# rotary-encoder-breakout-mk-2_0.net
KiCad netlist of a schematic drawn in EAGLE
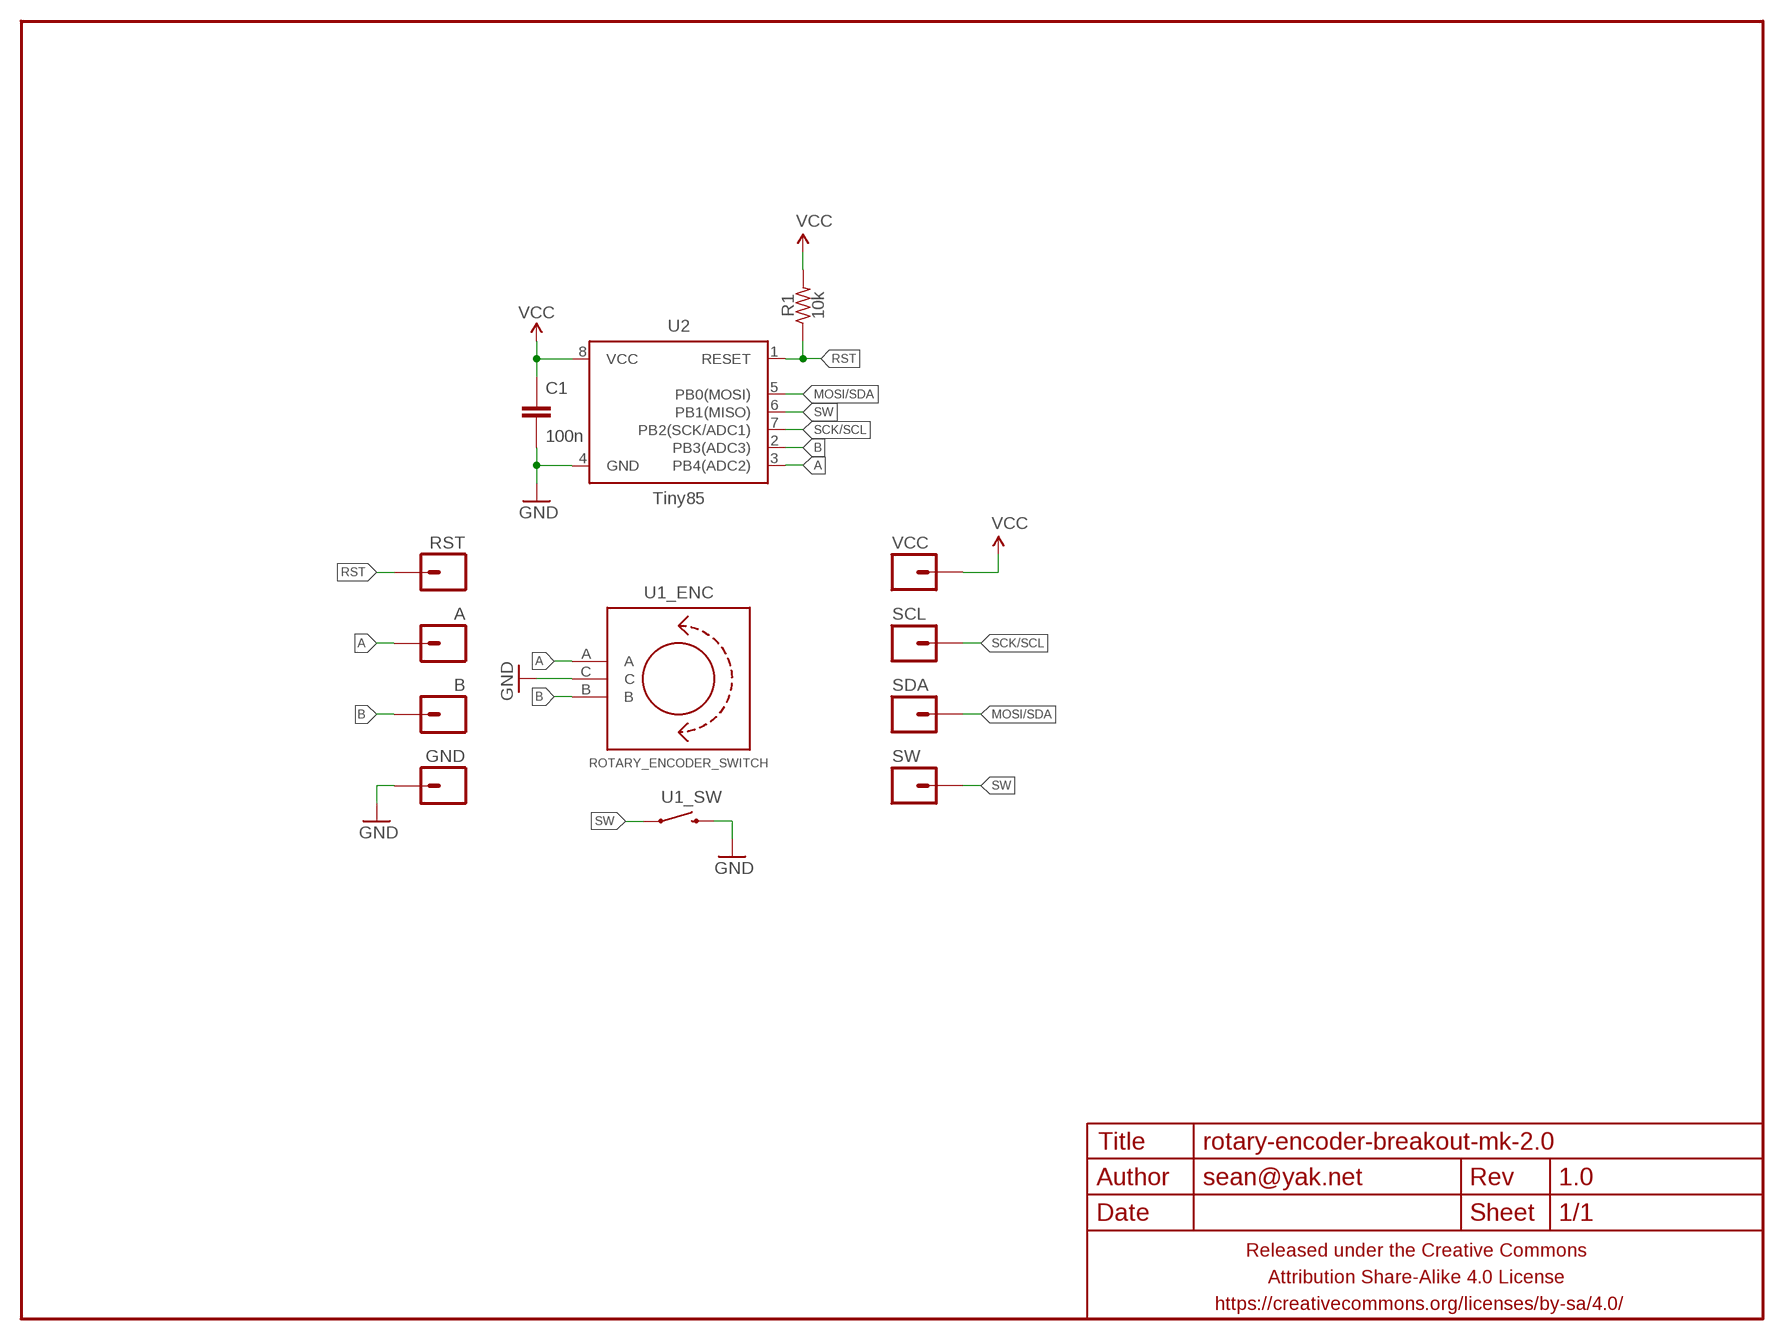
[diagram p0: schematic, sheet 1]

(export (version "E")
  (design (tool "Eeschema 10.0.6"))
  (components
    (comp (ref "A")
      (value "M01PTH-1MM")
      (footprint "eagle-import:1X01-1MM-NS")
      (libsource (lib "eagle-import") (part "M01PTH-1MM"))
    )
    (comp (ref "B")
      (value "M01PTH-1MM")
      (footprint "eagle-import:1X01-1MM-NS")
      (libsource (lib "eagle-import") (part "M01PTH-1MM"))
    )
    (comp (ref "C1")
      (value "100n")
      (footprint "eagle-import:C0603-TIGHTER")
      (libsource (lib "eagle-import") (part "CAPACITOR-CERAMICC0603-TIGHTER"))
    )
    (comp (ref "FRAME1")
      (value "FRAME-LETTERNO_PACKAGE")
      (footprint "eagle-import:DUMMY")
      (fields (field (name "DESIGNER") "sean@yak.net") (field (name "VERSION") "1.0"))
      (libsource (lib "eagle-import") (part "FRAME-LETTERNO_PACKAGE"))
    )
    (comp (ref "GND")
      (value "M01PTH-1MM")
      (footprint "eagle-import:1X01-1MM-NS")
      (libsource (lib "eagle-import") (part "M01PTH-1MM"))
    )
    (comp (ref "R1")
      (value "10k")
      (footprint "eagle-import:R0603-TIGHTER")
      (libsource (lib "eagle-import") (part "RESISTORR0603-TIGHTER"))
    )
    (comp (ref "RST")
      (value "M01PTH-1MM")
      (footprint "eagle-import:1X01-1MM-NS")
      (libsource (lib "eagle-import") (part "M01PTH-1MM"))
    )
    (comp (ref "SCL")
      (value "M01PTH-1MM")
      (footprint "eagle-import:1X01-1MM-NS")
      (libsource (lib "eagle-import") (part "M01PTH-1MM"))
    )
    (comp (ref "SDA")
      (value "M01PTH-1MM")
      (footprint "eagle-import:1X01-1MM-NS")
      (libsource (lib "eagle-import") (part "M01PTH-1MM"))
    )
    (comp (ref "SW")
      (value "M01PTH-1MM")
      (footprint "eagle-import:1X01-1MM-NS")
      (libsource (lib "eagle-import") (part "M01PTH-1MM"))
    )
    (comp (ref "U1_")
      (value "ROTARY_ENCODER_SWITCH")
      (footprint "eagle-import:ROTARY_ENCODER_SWITCH")
      (libsource (lib "eagle-import") (part "ROTARY_ENCODER_SWITCH"))
    )
    (comp (ref "U2")
      (value "Tiny85")
      (footprint "eagle-import:SO08-EIAJ")
      (libsource (lib "eagle-import") (part "ATTINY45TINY85-20-SOICW"))
    )
    (comp (ref "VCC")
      (value "M01PTH-1MM")
      (footprint "eagle-import:1X01-1MM-NS")
      (libsource (lib "eagle-import") (part "M01PTH-1MM"))
    )
  )
  (nets
    (net (code "1") (name "A") (class "Default")
      (node (ref "A") (pin "1") (pinfunction "1_1") (pintype "passive"))
      (node (ref "U1_") (pin "A") (pinfunction "A_A") (pintype "bidirectional"))
      (node (ref "U2") (pin "3") (pinfunction "PB4(ADC2)_3") (pintype "bidirectional"))
    )
    (net (code "2") (name "B") (class "Default")
      (node (ref "B") (pin "1") (pinfunction "1_1") (pintype "passive"))
      (node (ref "U1_") (pin "B") (pinfunction "B_B") (pintype "bidirectional"))
      (node (ref "U2") (pin "2") (pinfunction "PB3(ADC3)_2") (pintype "bidirectional"))
    )
    (net (code "3") (name "GND") (class "Default")
      (node (ref "C1") (pin "2") (pinfunction "2_2") (pintype "passive"))
      (node (ref "GND") (pin "1") (pinfunction "1_1") (pintype "passive"))
      (node (ref "U1_") (pin "C") (pinfunction "C_C") (pintype "bidirectional"))
      (node (ref "U1_") (pin "SW2") (pinfunction "2_SW2") (pintype "passive"))
      (node (ref "U2") (pin "4") (pinfunction "GND_4") (pintype "bidirectional"))
    )
    (net (code "4") (name "MOSI{slash}SDA") (class "Default")
      (node (ref "SDA") (pin "1") (pinfunction "1_1") (pintype "passive"))
      (node (ref "U2") (pin "5") (pinfunction "PB0(MOSI)_5") (pintype "bidirectional"))
    )
    (net (code "5") (name "RST") (class "Default")
      (node (ref "R1") (pin "1") (pinfunction "1_1") (pintype "passive"))
      (node (ref "RST") (pin "1") (pinfunction "1_1") (pintype "passive"))
      (node (ref "U2") (pin "1") (pinfunction "RESET_1") (pintype "bidirectional"))
    )
    (net (code "6") (name "SCK{slash}SCL") (class "Default")
      (node (ref "SCL") (pin "1") (pinfunction "1_1") (pintype "passive"))
      (node (ref "U2") (pin "7") (pinfunction "PB2(SCK/ADC1)_7") (pintype "bidirectional"))
    )
    (net (code "7") (name "SW") (class "Default")
      (node (ref "SW") (pin "1") (pinfunction "1_1") (pintype "passive"))
      (node (ref "U1_") (pin "SW1") (pinfunction "1_SW1") (pintype "passive"))
      (node (ref "U2") (pin "6") (pinfunction "PB1(MISO)_6") (pintype "bidirectional"))
    )
    (net (code "8") (name "VCC") (class "Default")
      (node (ref "C1") (pin "1") (pinfunction "1_1") (pintype "passive"))
      (node (ref "R1") (pin "2") (pinfunction "2_2") (pintype "passive"))
      (node (ref "U2") (pin "8") (pinfunction "VCC_8") (pintype "bidirectional"))
      (node (ref "VCC") (pin "1") (pinfunction "1_1") (pintype "passive"))
    )
  )
)
